# Groovegrid_pwr.net
KiCad netlist of a schematic drawn in EAGLE
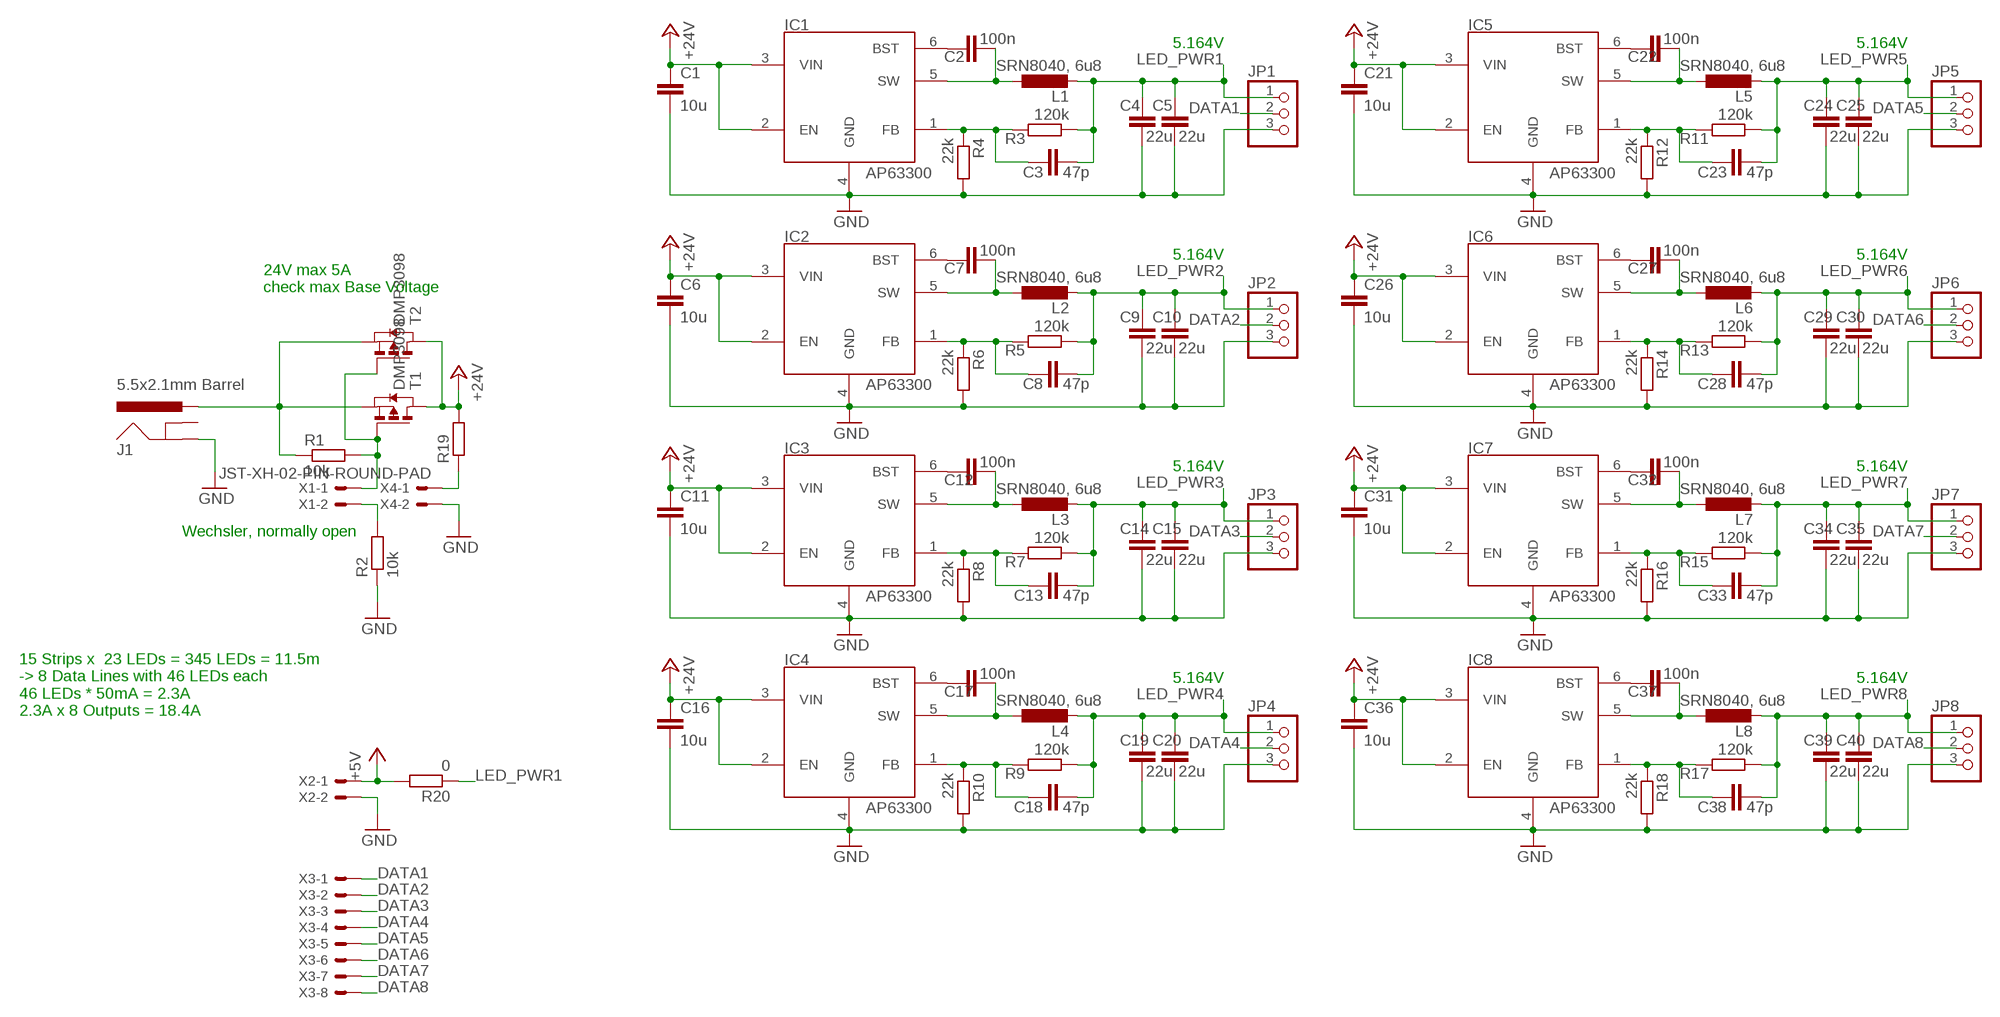
[diagram p0: schematic, sheet 1]

(export (version "E")
  (design (tool "Eeschema 10.0.6"))
  (components
    (comp (ref "C1")
      (value "10u")
      (footprint "eagle-import:C1206")
      (libsource (lib "eagle-import") (part "C-EUC1206"))
    )
    (comp (ref "C2")
      (value "100n")
      (footprint "eagle-import:C0805")
      (libsource (lib "eagle-import") (part "C-EUC0805"))
    )
    (comp (ref "C3")
      (value "47p")
      (footprint "eagle-import:C0805")
      (libsource (lib "eagle-import") (part "C-EUC0805"))
    )
    (comp (ref "C4")
      (value "22u")
      (footprint "eagle-import:C1206")
      (libsource (lib "eagle-import") (part "C-EUC1206"))
    )
    (comp (ref "C5")
      (value "22u")
      (footprint "eagle-import:C1206")
      (libsource (lib "eagle-import") (part "C-EUC1206"))
    )
    (comp (ref "C6")
      (value "10u")
      (footprint "eagle-import:C1206")
      (libsource (lib "eagle-import") (part "C-EUC1206"))
    )
    (comp (ref "C7")
      (value "100n")
      (footprint "eagle-import:C0805")
      (libsource (lib "eagle-import") (part "C-EUC0805"))
    )
    (comp (ref "C8")
      (value "47p")
      (footprint "eagle-import:C0805")
      (libsource (lib "eagle-import") (part "C-EUC0805"))
    )
    (comp (ref "C9")
      (value "22u")
      (footprint "eagle-import:C1206")
      (libsource (lib "eagle-import") (part "C-EUC1206"))
    )
    (comp (ref "C10")
      (value "22u")
      (footprint "eagle-import:C1206")
      (libsource (lib "eagle-import") (part "C-EUC1206"))
    )
    (comp (ref "C11")
      (value "10u")
      (footprint "eagle-import:C1206")
      (libsource (lib "eagle-import") (part "C-EUC1206"))
    )
    (comp (ref "C12")
      (value "100n")
      (footprint "eagle-import:C0805")
      (libsource (lib "eagle-import") (part "C-EUC0805"))
    )
    (comp (ref "C13")
      (value "47p")
      (footprint "eagle-import:C0805")
      (libsource (lib "eagle-import") (part "C-EUC0805"))
    )
    (comp (ref "C14")
      (value "22u")
      (footprint "eagle-import:C1206")
      (libsource (lib "eagle-import") (part "C-EUC1206"))
    )
    (comp (ref "C15")
      (value "22u")
      (footprint "eagle-import:C1206")
      (libsource (lib "eagle-import") (part "C-EUC1206"))
    )
    (comp (ref "C16")
      (value "10u")
      (footprint "eagle-import:C1206")
      (libsource (lib "eagle-import") (part "C-EUC1206"))
    )
    (comp (ref "C17")
      (value "100n")
      (footprint "eagle-import:C0805")
      (libsource (lib "eagle-import") (part "C-EUC0805"))
    )
    (comp (ref "C18")
      (value "47p")
      (footprint "eagle-import:C0805")
      (libsource (lib "eagle-import") (part "C-EUC0805"))
    )
    (comp (ref "C19")
      (value "22u")
      (footprint "eagle-import:C1206")
      (libsource (lib "eagle-import") (part "C-EUC1206"))
    )
    (comp (ref "C20")
      (value "22u")
      (footprint "eagle-import:C1206")
      (libsource (lib "eagle-import") (part "C-EUC1206"))
    )
    (comp (ref "C21")
      (value "10u")
      (footprint "eagle-import:C1206")
      (libsource (lib "eagle-import") (part "C-EUC1206"))
    )
    (comp (ref "C22")
      (value "100n")
      (footprint "eagle-import:C0805")
      (libsource (lib "eagle-import") (part "C-EUC0805"))
    )
    (comp (ref "C23")
      (value "47p")
      (footprint "eagle-import:C0805")
      (libsource (lib "eagle-import") (part "C-EUC0805"))
    )
    (comp (ref "C24")
      (value "22u")
      (footprint "eagle-import:C1206")
      (libsource (lib "eagle-import") (part "C-EUC1206"))
    )
    (comp (ref "C25")
      (value "22u")
      (footprint "eagle-import:C1206")
      (libsource (lib "eagle-import") (part "C-EUC1206"))
    )
    (comp (ref "C26")
      (value "10u")
      (footprint "eagle-import:C1206")
      (libsource (lib "eagle-import") (part "C-EUC1206"))
    )
    (comp (ref "C27")
      (value "100n")
      (footprint "eagle-import:C0805")
      (libsource (lib "eagle-import") (part "C-EUC0805"))
    )
    (comp (ref "C28")
      (value "47p")
      (footprint "eagle-import:C0805")
      (libsource (lib "eagle-import") (part "C-EUC0805"))
    )
    (comp (ref "C29")
      (value "22u")
      (footprint "eagle-import:C1206")
      (libsource (lib "eagle-import") (part "C-EUC1206"))
    )
    (comp (ref "C30")
      (value "22u")
      (footprint "eagle-import:C1206")
      (libsource (lib "eagle-import") (part "C-EUC1206"))
    )
    (comp (ref "C31")
      (value "10u")
      (footprint "eagle-import:C1206")
      (libsource (lib "eagle-import") (part "C-EUC1206"))
    )
    (comp (ref "C32")
      (value "100n")
      (footprint "eagle-import:C0805")
      (libsource (lib "eagle-import") (part "C-EUC0805"))
    )
    (comp (ref "C33")
      (value "47p")
      (footprint "eagle-import:C0805")
      (libsource (lib "eagle-import") (part "C-EUC0805"))
    )
    (comp (ref "C34")
      (value "22u")
      (footprint "eagle-import:C1206")
      (libsource (lib "eagle-import") (part "C-EUC1206"))
    )
    (comp (ref "C35")
      (value "22u")
      (footprint "eagle-import:C1206")
      (libsource (lib "eagle-import") (part "C-EUC1206"))
    )
    (comp (ref "C36")
      (value "10u")
      (footprint "eagle-import:C1206")
      (libsource (lib "eagle-import") (part "C-EUC1206"))
    )
    (comp (ref "C37")
      (value "100n")
      (footprint "eagle-import:C0805")
      (libsource (lib "eagle-import") (part "C-EUC0805"))
    )
    (comp (ref "C38")
      (value "47p")
      (footprint "eagle-import:C0805")
      (libsource (lib "eagle-import") (part "C-EUC0805"))
    )
    (comp (ref "C39")
      (value "22u")
      (footprint "eagle-import:C1206")
      (libsource (lib "eagle-import") (part "C-EUC1206"))
    )
    (comp (ref "C40")
      (value "22u")
      (footprint "eagle-import:C1206")
      (libsource (lib "eagle-import") (part "C-EUC1206"))
    )
    (comp (ref "IC1")
      (value "AP63300")
      (footprint "eagle-import:SOT23-6")
      (libsource (lib "eagle-import") (part "AP63300"))
    )
    (comp (ref "IC2")
      (value "AP63300")
      (footprint "eagle-import:SOT23-6")
      (libsource (lib "eagle-import") (part "AP63300"))
    )
    (comp (ref "IC3")
      (value "AP63300")
      (footprint "eagle-import:SOT23-6")
      (libsource (lib "eagle-import") (part "AP63300"))
    )
    (comp (ref "IC4")
      (value "AP63300")
      (footprint "eagle-import:SOT23-6")
      (libsource (lib "eagle-import") (part "AP63300"))
    )
    (comp (ref "IC5")
      (value "AP63300")
      (footprint "eagle-import:SOT23-6")
      (libsource (lib "eagle-import") (part "AP63300"))
    )
    (comp (ref "IC6")
      (value "AP63300")
      (footprint "eagle-import:SOT23-6")
      (libsource (lib "eagle-import") (part "AP63300"))
    )
    (comp (ref "IC7")
      (value "AP63300")
      (footprint "eagle-import:SOT23-6")
      (libsource (lib "eagle-import") (part "AP63300"))
    )
    (comp (ref "IC8")
      (value "AP63300")
      (footprint "eagle-import:SOT23-6")
      (libsource (lib "eagle-import") (part "AP63300"))
    )
    (comp (ref "J1")
      (value "5.5x2.1mm Barrel")
      (footprint "eagle-import:POWER_JACK_SMD")
      (libsource (lib "eagle-import") (part "POWER_JACKSMD"))
    )
    (comp (ref "JP1")
      (value "PINHD-1X3")
      (footprint "eagle-import:1X03")
      (libsource (lib "eagle-import") (part "PINHD-1X3"))
    )
    (comp (ref "JP2")
      (value "PINHD-1X3")
      (footprint "eagle-import:1X03")
      (libsource (lib "eagle-import") (part "PINHD-1X3"))
    )
    (comp (ref "JP3")
      (value "PINHD-1X3")
      (footprint "eagle-import:1X03")
      (libsource (lib "eagle-import") (part "PINHD-1X3"))
    )
    (comp (ref "JP4")
      (value "PINHD-1X3")
      (footprint "eagle-import:1X03")
      (libsource (lib "eagle-import") (part "PINHD-1X3"))
    )
    (comp (ref "JP5")
      (value "PINHD-1X3")
      (footprint "eagle-import:1X03")
      (libsource (lib "eagle-import") (part "PINHD-1X3"))
    )
    (comp (ref "JP6")
      (value "PINHD-1X3")
      (footprint "eagle-import:1X03")
      (libsource (lib "eagle-import") (part "PINHD-1X3"))
    )
    (comp (ref "JP7")
      (value "PINHD-1X3")
      (footprint "eagle-import:1X03")
      (libsource (lib "eagle-import") (part "PINHD-1X3"))
    )
    (comp (ref "JP8")
      (value "PINHD-1X3")
      (footprint "eagle-import:1X03")
      (libsource (lib "eagle-import") (part "PINHD-1X3"))
    )
    (comp (ref "L1")
      (value "SRN8040, 6u8")
      (footprint "eagle-import:SRN8040")
      (libsource (lib "eagle-import") (part "SRN8040"))
    )
    (comp (ref "L2")
      (value "SRN8040, 6u8")
      (footprint "eagle-import:SRN8040")
      (libsource (lib "eagle-import") (part "SRN8040"))
    )
    (comp (ref "L3")
      (value "SRN8040, 6u8")
      (footprint "eagle-import:SRN8040")
      (libsource (lib "eagle-import") (part "SRN8040"))
    )
    (comp (ref "L4")
      (value "SRN8040, 6u8")
      (footprint "eagle-import:SRN8040")
      (libsource (lib "eagle-import") (part "SRN8040"))
    )
    (comp (ref "L5")
      (value "SRN8040, 6u8")
      (footprint "eagle-import:SRN8040")
      (libsource (lib "eagle-import") (part "SRN8040"))
    )
    (comp (ref "L6")
      (value "SRN8040, 6u8")
      (footprint "eagle-import:SRN8040")
      (libsource (lib "eagle-import") (part "SRN8040"))
    )
    (comp (ref "L7")
      (value "SRN8040, 6u8")
      (footprint "eagle-import:SRN8040")
      (libsource (lib "eagle-import") (part "SRN8040"))
    )
    (comp (ref "L8")
      (value "SRN8040, 6u8")
      (footprint "eagle-import:SRN8040")
      (libsource (lib "eagle-import") (part "SRN8040"))
    )
    (comp (ref "R1")
      (value "10k")
      (footprint "eagle-import:R0805")
      (libsource (lib "eagle-import") (part "R-EU_R0805"))
    )
    (comp (ref "R2")
      (value "10k")
      (footprint "eagle-import:R0805")
      (libsource (lib "eagle-import") (part "R-EU_R0805"))
    )
    (comp (ref "R3")
      (value "120k")
      (footprint "eagle-import:R0805")
      (libsource (lib "eagle-import") (part "R-EU_R0805"))
    )
    (comp (ref "R4")
      (value "22k")
      (footprint "eagle-import:R0805")
      (libsource (lib "eagle-import") (part "R-EU_R0805"))
    )
    (comp (ref "R5")
      (value "120k")
      (footprint "eagle-import:R0805")
      (libsource (lib "eagle-import") (part "R-EU_R0805"))
    )
    (comp (ref "R6")
      (value "22k")
      (footprint "eagle-import:R0805")
      (libsource (lib "eagle-import") (part "R-EU_R0805"))
    )
    (comp (ref "R7")
      (value "120k")
      (footprint "eagle-import:R0805")
      (libsource (lib "eagle-import") (part "R-EU_R0805"))
    )
    (comp (ref "R8")
      (value "22k")
      (footprint "eagle-import:R0805")
      (libsource (lib "eagle-import") (part "R-EU_R0805"))
    )
    (comp (ref "R9")
      (value "120k")
      (footprint "eagle-import:R0805")
      (libsource (lib "eagle-import") (part "R-EU_R0805"))
    )
    (comp (ref "R10")
      (value "22k")
      (footprint "eagle-import:R0805")
      (libsource (lib "eagle-import") (part "R-EU_R0805"))
    )
    (comp (ref "R11")
      (value "120k")
      (footprint "eagle-import:R0805")
      (libsource (lib "eagle-import") (part "R-EU_R0805"))
    )
    (comp (ref "R12")
      (value "22k")
      (footprint "eagle-import:R0805")
      (libsource (lib "eagle-import") (part "R-EU_R0805"))
    )
    (comp (ref "R13")
      (value "120k")
      (footprint "eagle-import:R0805")
      (libsource (lib "eagle-import") (part "R-EU_R0805"))
    )
    (comp (ref "R14")
      (value "22k")
      (footprint "eagle-import:R0805")
      (libsource (lib "eagle-import") (part "R-EU_R0805"))
    )
    (comp (ref "R15")
      (value "120k")
      (footprint "eagle-import:R0805")
      (libsource (lib "eagle-import") (part "R-EU_R0805"))
    )
    (comp (ref "R16")
      (value "22k")
      (footprint "eagle-import:R0805")
      (libsource (lib "eagle-import") (part "R-EU_R0805"))
    )
    (comp (ref "R17")
      (value "120k")
      (footprint "eagle-import:R0805")
      (libsource (lib "eagle-import") (part "R-EU_R0805"))
    )
    (comp (ref "R18")
      (value "22k")
      (footprint "eagle-import:R0805")
      (libsource (lib "eagle-import") (part "R-EU_R0805"))
    )
    (comp (ref "R19")
      (value "R-EU_R0805")
      (footprint "eagle-import:R0805")
      (libsource (lib "eagle-import") (part "R-EU_R0805"))
    )
    (comp (ref "R20")
      (value "0")
      (footprint "eagle-import:R0805")
      (libsource (lib "eagle-import") (part "R-EU_R0805"))
    )
    (comp (ref "T1")
      (value "DMP3098")
      (footprint "eagle-import:SOT23-3")
      (libsource (lib "eagle-import") (part "PMOSSOT23"))
    )
    (comp (ref "T2")
      (value "DMP3098")
      (footprint "eagle-import:SOT23-3")
      (libsource (lib "eagle-import") (part "PMOSSOT23"))
    )
    (comp (ref "X1")
      (value "JST-XH-02-PIN-ROUND-PAD")
      (footprint "eagle-import:JST-XH-02-PACKAGE-ROUND-PAD")
      (libsource (lib "eagle-import") (part "JST-XH-02-PIN-ROUND-PAD"))
    )
    (comp (ref "X2")
      (value "JST-XH-02-PIN-ROUND-PAD")
      (footprint "eagle-import:JST-XH-02-PACKAGE-ROUND-PAD")
      (libsource (lib "eagle-import") (part "JST-XH-02-PIN-ROUND-PAD"))
    )
    (comp (ref "X3")
      (value "JST-XH-08-PIN-ROUND-PAD")
      (footprint "eagle-import:JST-XH-08-PACKAGE-ROUND-PAD")
      (libsource (lib "eagle-import") (part "JST-XH-08-PIN-ROUND-PAD"))
    )
    (comp (ref "X4")
      (value "JST-XH-02-PIN-ROUND-PAD")
      (footprint "eagle-import:JST-XH-02-PACKAGE-ROUND-PAD")
      (libsource (lib "eagle-import") (part "JST-XH-02-PIN-ROUND-PAD"))
    )
  )
  (nets
    (net (code "1") (name "+5V") (class "Default")
      (node (ref "R20") (pin "2") (pinfunction "2_2") (pintype "passive"))
      (node (ref "X2") (pin "1") (pinfunction "S_1") (pintype "passive"))
    )
    (net (code "2") (name "+24V") (class "Default")
      (node (ref "C1") (pin "1") (pinfunction "1_1") (pintype "passive"))
      (node (ref "C11") (pin "1") (pinfunction "1_1") (pintype "passive"))
      (node (ref "C16") (pin "1") (pinfunction "1_1") (pintype "passive"))
      (node (ref "C21") (pin "1") (pinfunction "1_1") (pintype "passive"))
      (node (ref "C26") (pin "1") (pinfunction "1_1") (pintype "passive"))
      (node (ref "C31") (pin "1") (pinfunction "1_1") (pintype "passive"))
      (node (ref "C36") (pin "1") (pinfunction "1_1") (pintype "passive"))
      (node (ref "C6") (pin "1") (pinfunction "1_1") (pintype "passive"))
      (node (ref "IC1") (pin "2") (pinfunction "EN_2") (pintype "bidirectional"))
      (node (ref "IC1") (pin "3") (pinfunction "VIN_3") (pintype "bidirectional"))
      (node (ref "IC2") (pin "2") (pinfunction "EN_2") (pintype "bidirectional"))
      (node (ref "IC2") (pin "3") (pinfunction "VIN_3") (pintype "bidirectional"))
      (node (ref "IC3") (pin "2") (pinfunction "EN_2") (pintype "bidirectional"))
      (node (ref "IC3") (pin "3") (pinfunction "VIN_3") (pintype "bidirectional"))
      (node (ref "IC4") (pin "2") (pinfunction "EN_2") (pintype "bidirectional"))
      (node (ref "IC4") (pin "3") (pinfunction "VIN_3") (pintype "bidirectional"))
      (node (ref "IC5") (pin "2") (pinfunction "EN_2") (pintype "bidirectional"))
      (node (ref "IC5") (pin "3") (pinfunction "VIN_3") (pintype "bidirectional"))
      (node (ref "IC6") (pin "2") (pinfunction "EN_2") (pintype "bidirectional"))
      (node (ref "IC6") (pin "3") (pinfunction "VIN_3") (pintype "bidirectional"))
      (node (ref "IC7") (pin "2") (pinfunction "EN_2") (pintype "bidirectional"))
      (node (ref "IC7") (pin "3") (pinfunction "VIN_3") (pintype "bidirectional"))
      (node (ref "IC8") (pin "2") (pinfunction "EN_2") (pintype "bidirectional"))
      (node (ref "IC8") (pin "3") (pinfunction "VIN_3") (pintype "bidirectional"))
      (node (ref "R19") (pin "2") (pinfunction "2_2") (pintype "passive"))
      (node (ref "T1") (pin "3") (pinfunction "D_3") (pintype "passive"))
      (node (ref "T2") (pin "3") (pinfunction "D_3") (pintype "passive"))
    )
    (net (code "3") (name "/DATA1") (class "Default")
      (node (ref "JP1") (pin "2") (pinfunction "2_2") (pintype "passive"))
      (node (ref "X3") (pin "1") (pinfunction "S_1") (pintype "passive"))
    )
    (net (code "4") (name "/DATA2") (class "Default")
      (node (ref "JP2") (pin "2") (pinfunction "2_2") (pintype "passive"))
      (node (ref "X3") (pin "2") (pinfunction "S_2") (pintype "passive"))
    )
    (net (code "5") (name "/DATA3") (class "Default")
      (node (ref "JP3") (pin "2") (pinfunction "2_2") (pintype "passive"))
      (node (ref "X3") (pin "3") (pinfunction "S_3") (pintype "passive"))
    )
    (net (code "6") (name "/DATA4") (class "Default")
      (node (ref "JP4") (pin "2") (pinfunction "2_2") (pintype "passive"))
      (node (ref "X3") (pin "4") (pinfunction "S_4") (pintype "passive"))
    )
    (net (code "7") (name "/DATA5") (class "Default")
      (node (ref "JP5") (pin "2") (pinfunction "2_2") (pintype "passive"))
      (node (ref "X3") (pin "5") (pinfunction "S_5") (pintype "passive"))
    )
    (net (code "8") (name "/DATA6") (class "Default")
      (node (ref "JP6") (pin "2") (pinfunction "2_2") (pintype "passive"))
      (node (ref "X3") (pin "6") (pinfunction "S_6") (pintype "passive"))
    )
    (net (code "9") (name "/DATA7") (class "Default")
      (node (ref "JP7") (pin "2") (pinfunction "2_2") (pintype "passive"))
      (node (ref "X3") (pin "7") (pinfunction "S_7") (pintype "passive"))
    )
    (net (code "10") (name "/DATA8") (class "Default")
      (node (ref "JP8") (pin "2") (pinfunction "2_2") (pintype "passive"))
      (node (ref "X3") (pin "8") (pinfunction "S_8") (pintype "passive"))
    )
    (net (code "11") (name "/LED_PWR1") (class "Default")
      (node (ref "C3") (pin "2") (pinfunction "2_2") (pintype "passive"))
      (node (ref "C4") (pin "1") (pinfunction "1_1") (pintype "passive"))
      (node (ref "C5") (pin "1") (pinfunction "1_1") (pintype "passive"))
      (node (ref "JP1") (pin "1") (pinfunction "1_1") (pintype "passive"))
      (node (ref "L1") (pin "P$2") (pinfunction "2_P$2") (pintype "passive"))
      (node (ref "R20") (pin "1") (pinfunction "1_1") (pintype "passive"))
      (node (ref "R3") (pin "1") (pinfunction "1_1") (pintype "passive"))
    )
    (net (code "12") (name "/LED_PWR2") (class "Default")
      (node (ref "C10") (pin "1") (pinfunction "1_1") (pintype "passive"))
      (node (ref "C8") (pin "2") (pinfunction "2_2") (pintype "passive"))
      (node (ref "C9") (pin "1") (pinfunction "1_1") (pintype "passive"))
      (node (ref "JP2") (pin "1") (pinfunction "1_1") (pintype "passive"))
      (node (ref "L2") (pin "P$2") (pinfunction "2_P$2") (pintype "passive"))
      (node (ref "R5") (pin "1") (pinfunction "1_1") (pintype "passive"))
    )
    (net (code "13") (name "/LED_PWR3") (class "Default")
      (node (ref "C13") (pin "2") (pinfunction "2_2") (pintype "passive"))
      (node (ref "C14") (pin "1") (pinfunction "1_1") (pintype "passive"))
      (node (ref "C15") (pin "1") (pinfunction "1_1") (pintype "passive"))
      (node (ref "JP3") (pin "1") (pinfunction "1_1") (pintype "passive"))
      (node (ref "L3") (pin "P$2") (pinfunction "2_P$2") (pintype "passive"))
      (node (ref "R7") (pin "1") (pinfunction "1_1") (pintype "passive"))
    )
    (net (code "14") (name "/LED_PWR4") (class "Default")
      (node (ref "C18") (pin "2") (pinfunction "2_2") (pintype "passive"))
      (node (ref "C19") (pin "1") (pinfunction "1_1") (pintype "passive"))
      (node (ref "C20") (pin "1") (pinfunction "1_1") (pintype "passive"))
      (node (ref "JP4") (pin "1") (pinfunction "1_1") (pintype "passive"))
      (node (ref "L4") (pin "P$2") (pinfunction "2_P$2") (pintype "passive"))
      (node (ref "R9") (pin "1") (pinfunction "1_1") (pintype "passive"))
    )
    (net (code "15") (name "/LED_PWR5") (class "Default")
      (node (ref "C23") (pin "2") (pinfunction "2_2") (pintype "passive"))
      (node (ref "C24") (pin "1") (pinfunction "1_1") (pintype "passive"))
      (node (ref "C25") (pin "1") (pinfunction "1_1") (pintype "passive"))
      (node (ref "JP5") (pin "1") (pinfunction "1_1") (pintype "passive"))
      (node (ref "L5") (pin "P$2") (pinfunction "2_P$2") (pintype "passive"))
      (node (ref "R11") (pin "1") (pinfunction "1_1") (pintype "passive"))
    )
    (net (code "16") (name "/LED_PWR6") (class "Default")
      (node (ref "C28") (pin "2") (pinfunction "2_2") (pintype "passive"))
      (node (ref "C29") (pin "1") (pinfunction "1_1") (pintype "passive"))
      (node (ref "C30") (pin "1") (pinfunction "1_1") (pintype "passive"))
      (node (ref "JP6") (pin "1") (pinfunction "1_1") (pintype "passive"))
      (node (ref "L6") (pin "P$2") (pinfunction "2_P$2") (pintype "passive"))
      (node (ref "R13") (pin "1") (pinfunction "1_1") (pintype "passive"))
    )
    (net (code "17") (name "/LED_PWR7") (class "Default")
      (node (ref "C33") (pin "2") (pinfunction "2_2") (pintype "passive"))
      (node (ref "C34") (pin "1") (pinfunction "1_1") (pintype "passive"))
      (node (ref "C35") (pin "1") (pinfunction "1_1") (pintype "passive"))
      (node (ref "JP7") (pin "1") (pinfunction "1_1") (pintype "passive"))
      (node (ref "L7") (pin "P$2") (pinfunction "2_P$2") (pintype "passive"))
      (node (ref "R15") (pin "1") (pinfunction "1_1") (pintype "passive"))
    )
    (net (code "18") (name "/LED_PWR8") (class "Default")
      (node (ref "C38") (pin "2") (pinfunction "2_2") (pintype "passive"))
      (node (ref "C39") (pin "1") (pinfunction "1_1") (pintype "passive"))
      (node (ref "C40") (pin "1") (pinfunction "1_1") (pintype "passive"))
      (node (ref "JP8") (pin "1") (pinfunction "1_1") (pintype "passive"))
      (node (ref "L8") (pin "P$2") (pinfunction "2_P$2") (pintype "passive"))
      (node (ref "R17") (pin "1") (pinfunction "1_1") (pintype "passive"))
    )
    (net (code "19") (name "GND") (class "Default")
      (node (ref "C1") (pin "2") (pinfunction "2_2") (pintype "passive"))
      (node (ref "C10") (pin "2") (pinfunction "2_2") (pintype "passive"))
      (node (ref "C11") (pin "2") (pinfunction "2_2") (pintype "passive"))
      (node (ref "C14") (pin "2") (pinfunction "2_2") (pintype "passive"))
      (node (ref "C15") (pin "2") (pinfunction "2_2") (pintype "passive"))
      (node (ref "C16") (pin "2") (pinfunction "2_2") (pintype "passive"))
      (node (ref "C19") (pin "2") (pinfunction "2_2") (pintype "passive"))
      (node (ref "C20") (pin "2") (pinfunction "2_2") (pintype "passive"))
      (node (ref "C21") (pin "2") (pinfunction "2_2") (pintype "passive"))
      (node (ref "C24") (pin "2") (pinfunction "2_2") (pintype "passive"))
      (node (ref "C25") (pin "2") (pinfunction "2_2") (pintype "passive"))
      (node (ref "C26") (pin "2") (pinfunction "2_2") (pintype "passive"))
      (node (ref "C29") (pin "2") (pinfunction "2_2") (pintype "passive"))
      (node (ref "C30") (pin "2") (pinfunction "2_2") (pintype "passive"))
      (node (ref "C31") (pin "2") (pinfunction "2_2") (pintype "passive"))
      (node (ref "C34") (pin "2") (pinfunction "2_2") (pintype "passive"))
      (node (ref "C35") (pin "2") (pinfunction "2_2") (pintype "passive"))
      (node (ref "C36") (pin "2") (pinfunction "2_2") (pintype "passive"))
      (node (ref "C39") (pin "2") (pinfunction "2_2") (pintype "passive"))
      (node (ref "C4") (pin "2") (pinfunction "2_2") (pintype "passive"))
      (node (ref "C40") (pin "2") (pinfunction "2_2") (pintype "passive"))
      (node (ref "C5") (pin "2") (pinfunction "2_2") (pintype "passive"))
      (node (ref "C6") (pin "2") (pinfunction "2_2") (pintype "passive"))
      (node (ref "C9") (pin "2") (pinfunction "2_2") (pintype "passive"))
      (node (ref "IC1") (pin "4") (pinfunction "GND_4") (pintype "bidirectional"))
      (node (ref "IC2") (pin "4") (pinfunction "GND_4") (pintype "bidirectional"))
      (node (ref "IC3") (pin "4") (pinfunction "GND_4") (pintype "bidirectional"))
      (node (ref "IC4") (pin "4") (pinfunction "GND_4") (pintype "bidirectional"))
      (node (ref "IC5") (pin "4") (pinfunction "GND_4") (pintype "bidirectional"))
      (node (ref "IC6") (pin "4") (pinfunction "GND_4") (pintype "bidirectional"))
      (node (ref "IC7") (pin "4") (pinfunction "GND_4") (pintype "bidirectional"))
      (node (ref "IC8") (pin "4") (pinfunction "GND_4") (pintype "bidirectional"))
      (node (ref "J1") (pin "VIN-") (pinfunction "VIN-_VIN-") (pintype "bidirectional"))
      (node (ref "JP1") (pin "3") (pinfunction "3_3") (pintype "passive"))
      (node (ref "JP2") (pin "3") (pinfunction "3_3") (pintype "passive"))
      (node (ref "JP3") (pin "3") (pinfunction "3_3") (pintype "passive"))
      (node (ref "JP4") (pin "3") (pinfunction "3_3") (pintype "passive"))
      (node (ref "JP5") (pin "3") (pinfunction "3_3") (pintype "passive"))
      (node (ref "JP6") (pin "3") (pinfunction "3_3") (pintype "passive"))
      (node (ref "JP7") (pin "3") (pinfunction "3_3") (pintype "passive"))
      (node (ref "JP8") (pin "3") (pinfunction "3_3") (pintype "passive"))
      (node (ref "R10") (pin "2") (pinfunction "2_2") (pintype "passive"))
      (node (ref "R12") (pin "2") (pinfunction "2_2") (pintype "passive"))
      (node (ref "R14") (pin "2") (pinfunction "2_2") (pintype "passive"))
      (node (ref "R16") (pin "2") (pinfunction "2_2") (pintype "passive"))
      (node (ref "R18") (pin "2") (pinfunction "2_2") (pintype "passive"))
      (node (ref "R2") (pin "1") (pinfunction "1_1") (pintype "passive"))
      (node (ref "R4") (pin "2") (pinfunction "2_2") (pintype "passive"))
      (node (ref "R6") (pin "2") (pinfunction "2_2") (pintype "passive"))
      (node (ref "R8") (pin "2") (pinfunction "2_2") (pintype "passive"))
      (node (ref "X2") (pin "2") (pinfunction "S_2") (pintype "passive"))
      (node (ref "X4") (pin "2") (pinfunction "S_2") (pintype "passive"))
    )
    (net (code "20") (name "Net-(IC1-BST)") (class "Default")
      (node (ref "C2") (pin "1") (pinfunction "1_1") (pintype "passive"))
      (node (ref "IC1") (pin "6") (pinfunction "BST_6") (pintype "bidirectional"))
    )
    (net (code "21") (name "Net-(IC1-FB)") (class "Default")
      (node (ref "C3") (pin "1") (pinfunction "1_1") (pintype "passive"))
      (node (ref "IC1") (pin "1") (pinfunction "FB_1") (pintype "bidirectional"))
      (node (ref "R3") (pin "2") (pinfunction "2_2") (pintype "passive"))
      (node (ref "R4") (pin "1") (pinfunction "1_1") (pintype "passive"))
    )
    (net (code "22") (name "Net-(IC1-SW)") (class "Default")
      (node (ref "C2") (pin "2") (pinfunction "2_2") (pintype "passive"))
      (node (ref "IC1") (pin "5") (pinfunction "SW_5") (pintype "bidirectional"))
      (node (ref "L1") (pin "P$1") (pinfunction "1_P$1") (pintype "passive"))
    )
    (net (code "23") (name "Net-(IC2-BST)") (class "Default")
      (node (ref "C7") (pin "1") (pinfunction "1_1") (pintype "passive"))
      (node (ref "IC2") (pin "6") (pinfunction "BST_6") (pintype "bidirectional"))
    )
    (net (code "24") (name "Net-(IC2-FB)") (class "Default")
      (node (ref "C8") (pin "1") (pinfunction "1_1") (pintype "passive"))
      (node (ref "IC2") (pin "1") (pinfunction "FB_1") (pintype "bidirectional"))
      (node (ref "R5") (pin "2") (pinfunction "2_2") (pintype "passive"))
      (node (ref "R6") (pin "1") (pinfunction "1_1") (pintype "passive"))
    )
    (net (code "25") (name "Net-(IC2-SW)") (class "Default")
      (node (ref "C7") (pin "2") (pinfunction "2_2") (pintype "passive"))
      (node (ref "IC2") (pin "5") (pinfunction "SW_5") (pintype "bidirectional"))
      (node (ref "L2") (pin "P$1") (pinfunction "1_P$1") (pintype "passive"))
    )
    (net (code "26") (name "Net-(IC3-BST)") (class "Default")
      (node (ref "C12") (pin "1") (pinfunction "1_1") (pintype "passive"))
      (node (ref "IC3") (pin "6") (pinfunction "BST_6") (pintype "bidirectional"))
    )
    (net (code "27") (name "Net-(IC3-FB)") (class "Default")
      (node (ref "C13") (pin "1") (pinfunction "1_1") (pintype "passive"))
      (node (ref "IC3") (pin "1") (pinfunction "FB_1") (pintype "bidirectional"))
      (node (ref "R7") (pin "2") (pinfunction "2_2") (pintype "passive"))
      (node (ref "R8") (pin "1") (pinfunction "1_1") (pintype "passive"))
    )
    (net (code "28") (name "Net-(IC3-SW)") (class "Default")
      (node (ref "C12") (pin "2") (pinfunction "2_2") (pintype "passive"))
      (node (ref "IC3") (pin "5") (pinfunction "SW_5") (pintype "bidirectional"))
      (node (ref "L3") (pin "P$1") (pinfunction "1_P$1") (pintype "passive"))
    )
    (net (code "29") (name "Net-(IC4-BST)") (class "Default")
      (node (ref "C17") (pin "1") (pinfunction "1_1") (pintype "passive"))
      (node (ref "IC4") (pin "6") (pinfunction "BST_6") (pintype "bidirectional"))
    )
    (net (code "30") (name "Net-(IC4-FB)") (class "Default")
      (node (ref "C18") (pin "1") (pinfunction "1_1") (pintype "passive"))
      (node (ref "IC4") (pin "1") (pinfunction "FB_1") (pintype "bidirectional"))
      (node (ref "R10") (pin "1") (pinfunction "1_1") (pintype "passive"))
      (node (ref "R9") (pin "2") (pinfunction "2_2") (pintype "passive"))
    )
    (net (code "31") (name "Net-(IC4-SW)") (class "Default")
      (node (ref "C17") (pin "2") (pinfunction "2_2") (pintype "passive"))
      (node (ref "IC4") (pin "5") (pinfunction "SW_5") (pintype "bidirectional"))
      (node (ref "L4") (pin "P$1") (pinfunction "1_P$1") (pintype "passive"))
    )
    (net (code "32") (name "Net-(IC5-BST)") (class "Default")
      (node (ref "C22") (pin "1") (pinfunction "1_1") (pintype "passive"))
      (node (ref "IC5") (pin "6") (pinfunction "BST_6") (pintype "bidirectional"))
    )
    (net (code "33") (name "Net-(IC5-FB)") (class "Default")
      (node (ref "C23") (pin "1") (pinfunction "1_1") (pintype "passive"))
      (node (ref "IC5") (pin "1") (pinfunction "FB_1") (pintype "bidirectional"))
      (node (ref "R11") (pin "2") (pinfunction "2_2") (pintype "passive"))
      (node (ref "R12") (pin "1") (pinfunction "1_1") (pintype "passive"))
    )
    (net (code "34") (name "Net-(IC5-SW)") (class "Default")
      (node (ref "C22") (pin "2") (pinfunction "2_2") (pintype "passive"))
      (node (ref "IC5") (pin "5") (pinfunction "SW_5") (pintype "bidirectional"))
      (node (ref "L5") (pin "P$1") (pinfunction "1_P$1") (pintype "passive"))
    )
    (net (code "35") (name "Net-(IC6-BST)") (class "Default")
      (node (ref "C27") (pin "1") (pinfunction "1_1") (pintype "passive"))
      (node (ref "IC6") (pin "6") (pinfunction "BST_6") (pintype "bidirectional"))
    )
    (net (code "36") (name "Net-(IC6-FB)") (class "Default")
      (node (ref "C28") (pin "1") (pinfunction "1_1") (pintype "passive"))
      (node (ref "IC6") (pin "1") (pinfunction "FB_1") (pintype "bidirectional"))
      (node (ref "R13") (pin "2") (pinfunction "2_2") (pintype "passive"))
      (node (ref "R14") (pin "1") (pinfunction "1_1") (pintype "passive"))
    )
    (net (code "37") (name "Net-(IC6-SW)") (class "Default")
      (node (ref "C27") (pin "2") (pinfunction "2_2") (pintype "passive"))
      (node (ref "IC6") (pin "5") (pinfunction "SW_5") (pintype "bidirectional"))
      (node (ref "L6") (pin "P$1") (pinfunction "1_P$1") (pintype "passive"))
    )
    (net (code "38") (name "Net-(IC7-BST)") (class "Default")
      (node (ref "C32") (pin "1") (pinfunction "1_1") (pintype "passive"))
      (node (ref "IC7") (pin "6") (pinfunction "BST_6") (pintype "bidirectional"))
    )
    (net (code "39") (name "Net-(IC7-FB)") (class "Default")
      (node (ref "C33") (pin "1") (pinfunction "1_1") (pintype "passive"))
      (node (ref "IC7") (pin "1") (pinfunction "FB_1") (pintype "bidirectional"))
      (node (ref "R15") (pin "2") (pinfunction "2_2") (pintype "passive"))
      (node (ref "R16") (pin "1") (pinfunction "1_1") (pintype "passive"))
    )
    (net (code "40") (name "Net-(IC7-SW)") (class "Default")
      (node (ref "C32") (pin "2") (pinfunction "2_2") (pintype "passive"))
      (node (ref "IC7") (pin "5") (pinfunction "SW_5") (pintype "bidirectional"))
      (node (ref "L7") (pin "P$1") (pinfunction "1_P$1") (pintype "passive"))
    )
    (net (code "41") (name "Net-(IC8-BST)") (class "Default")
      (node (ref "C37") (pin "1") (pinfunction "1_1") (pintype "passive"))
      (node (ref "IC8") (pin "6") (pinfunction "BST_6") (pintype "bidirectional"))
    )
    (net (code "42") (name "Net-(IC8-FB)") (class "Default")
      (node (ref "C38") (pin "1") (pinfunction "1_1") (pintype "passive"))
      (node (ref "IC8") (pin "1") (pinfunction "FB_1") (pintype "bidirectional"))
      (node (ref "R17") (pin "2") (pinfunction "2_2") (pintype "passive"))
      (node (ref "R18") (pin "1") (pinfunction "1_1") (pintype "passive"))
    )
    (net (code "43") (name "Net-(IC8-SW)") (class "Default")
      (node (ref "C37") (pin "2") (pinfunction "2_2") (pintype "passive"))
      (node (ref "IC8") (pin "5") (pinfunction "SW_5") (pintype "bidirectional"))
      (node (ref "L8") (pin "P$1") (pinfunction "1_P$1") (pintype "passive"))
    )
    (net (code "44") (name "Net-(T1-G)") (class "Default")
      (node (ref "R1") (pin "2") (pinfunction "2_2") (pintype "passive"))
      (node (ref "T1") (pin "1") (pinfunction "G_1") (pintype "passive"))
      (node (ref "T2") (pin "1") (pinfunction "G_1") (pintype "passive"))
      (node (ref "X1") (pin "1") (pinfunction "S_1") (pintype "passive"))
    )
    (net (code "45") (name "Net-(T1-S)") (class "Default")
      (node (ref "J1") (pin "VIN+0") (pinfunction "VIN+_VIN+0") (pintype "bidirectional"))
      (node (ref "J1") (pin "VIN+1") (pinfunction "VIN+_VIN+1") (pintype "bidirectional"))
      (node (ref "R1") (pin "1") (pinfunction "1_1") (pintype "passive"))
      (node (ref "T1") (pin "2") (pinfunction "S_2") (pintype "passive"))
      (node (ref "T2") (pin "2") (pinfunction "S_2") (pintype "passive"))
    )
    (net (code "46") (name "Net-(X1B-S)") (class "Default")
      (node (ref "R2") (pin "2") (pinfunction "2_2") (pintype "passive"))
      (node (ref "X1") (pin "2") (pinfunction "S_2") (pintype "passive"))
    )
    (net (code "47") (name "Net-(X4A-S)") (class "Default")
      (node (ref "R19") (pin "1") (pinfunction "1_1") (pintype "passive"))
      (node (ref "X4") (pin "1") (pinfunction "S_1") (pintype "passive"))
    )
    (net (code "48") (name "unconnected-(J1-PadDET)") (class "Default")
      (node (ref "J1") (pin "DET") (pinfunction "DET_DET") (pintype "bidirectional"))
    )
  )
)
